# usb_host_otg.net
KiCad netlist of a schematic drawn in Altium Designer
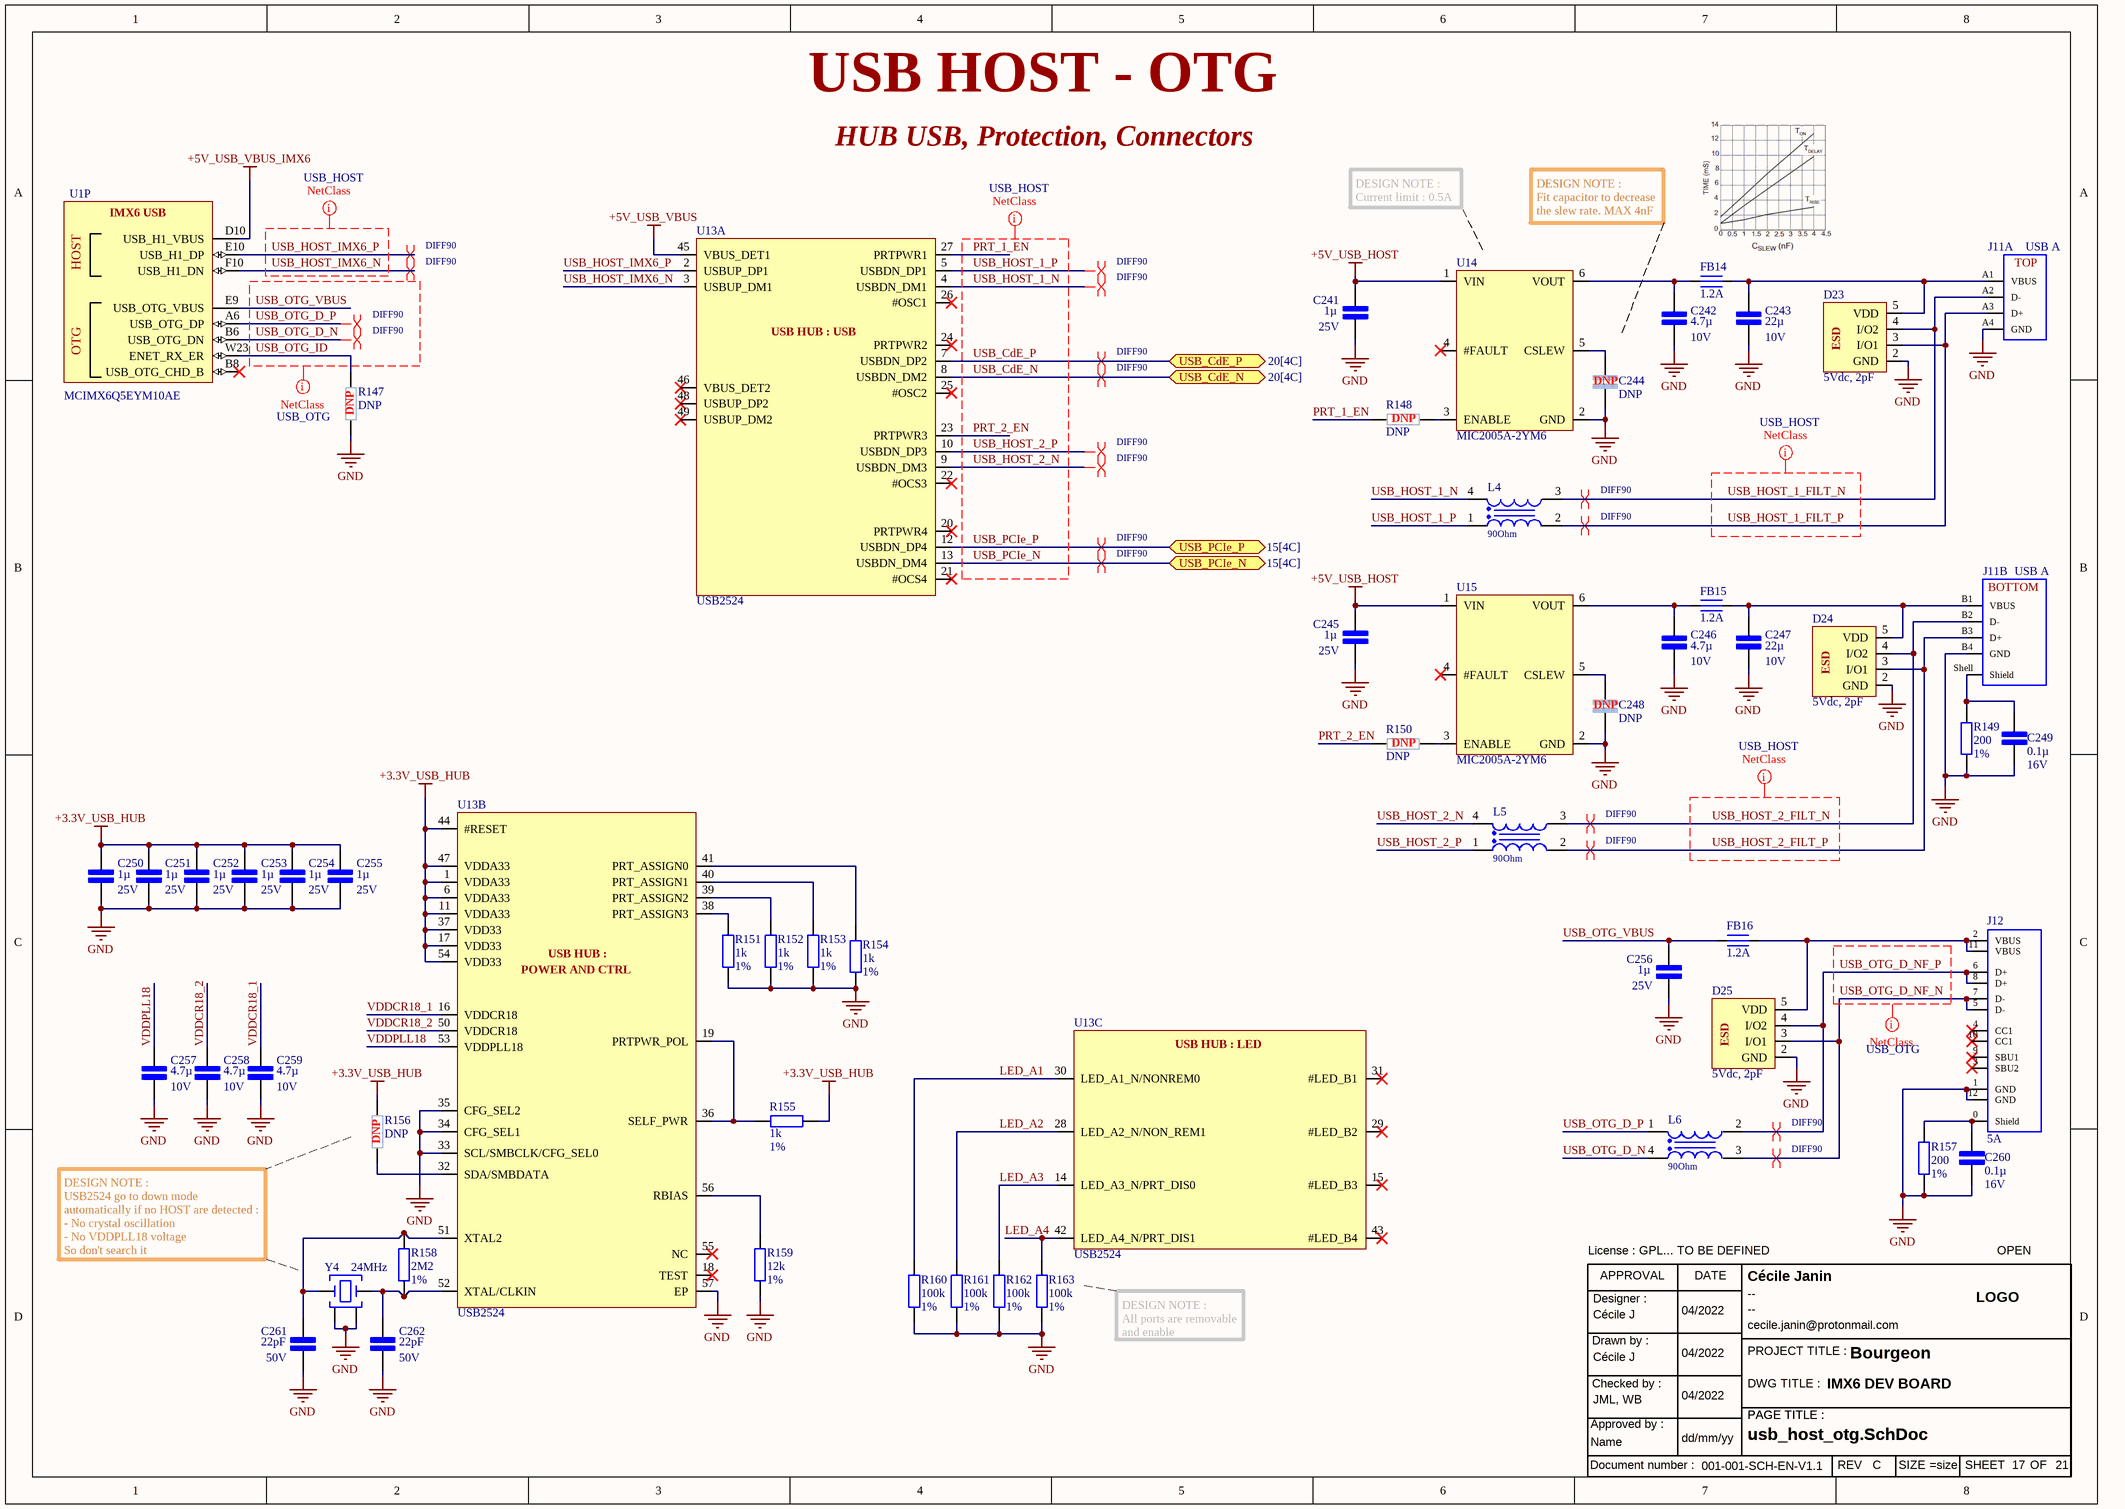
[diagram p0: usb_host_otg.SchDoc]

(export (version "E")
  (design (tool "Eeschema 10.0.6"))
  (components
    (comp (ref "C241")
      (value "1µ")
      (footprint "Cap cer 0402/1005")
      (description "cap cer 1µ 25V 10% X5R 0402")
      (fields (field (name "TENSION DU DIÉLECTRIQUE") "25V"))
      (libsource (lib "First Board IMX6") (part "cap 1µ 25V"))
    )
    (comp (ref "C242")
      (value "4.7µ")
      (footprint "Cap cer 0402/1005")
      (description "cap cer 4.7µ 10V 10% X7R 0402")
      (fields (field (name "TENSION DU DIÉLECTRIQUE") "10V"))
      (libsource (lib "First Board IMX6") (part "cap 4.7µ 10V"))
    )
    (comp (ref "C243")
      (value "22µ")
      (footprint "Cap cer 0603/4608")
      (description "cap cer 22µ 10V 10% X5R 0603")
      (fields (field (name "TENSION DU DIÉLECTRIQUE") "10V"))
      (libsource (lib "First Board IMX6") (part "cap 22µ 10V"))
    )
    (comp (ref "C244")
      (value "DNP")
      (footprint "Cap cer 0402/1005")
      (description "cap cer DNP 0402")
      (libsource (lib "First Board IMX6") (part "cap DNP"))
    )
    (comp (ref "C245")
      (value "1µ")
      (footprint "Cap cer 0402/1005")
      (description "cap cer 1µ 25V 10% X5R 0402")
      (fields (field (name "TENSION DU DIÉLECTRIQUE") "25V"))
      (libsource (lib "First Board IMX6") (part "cap 1µ 25V"))
    )
    (comp (ref "C246")
      (value "4.7µ")
      (footprint "Cap cer 0402/1005")
      (description "cap cer 4.7µ 10V 10% X7R 0402")
      (fields (field (name "TENSION DU DIÉLECTRIQUE") "10V"))
      (libsource (lib "First Board IMX6") (part "cap 4.7µ 10V"))
    )
    (comp (ref "C247")
      (value "22µ")
      (footprint "Cap cer 0603/4608")
      (description "cap cer 22µ 10V 10% X5R 0603")
      (fields (field (name "TENSION DU DIÉLECTRIQUE") "10V"))
      (libsource (lib "First Board IMX6") (part "cap 22µ 10V"))
    )
    (comp (ref "C248")
      (value "DNP")
      (footprint "Cap cer 0402/1005")
      (description "cap cer DNP 0402")
      (libsource (lib "First Board IMX6") (part "cap DNP"))
    )
    (comp (ref "C249")
      (value "0.1µ")
      (footprint "Cap cer 0402/1005")
      (description "cap solid electrolyte 0.1µ 6.3V 10%")
      (fields (field (name "TENSION DU DIÉLECTRIQUE") "16V"))
      (libsource (lib "First Board IMX6") (part "cap 0.1µ 16V"))
    )
    (comp (ref "C250")
      (value "1µ")
      (footprint "Cap cer 0402/1005")
      (description "cap cer 1µ 25V 10% X5R 0402")
      (fields (field (name "TENSION DU DIÉLECTRIQUE") "25V"))
      (libsource (lib "First Board IMX6") (part "cap 1µ 25V"))
    )
    (comp (ref "C251")
      (value "1µ")
      (footprint "Cap cer 0402/1005")
      (description "cap cer 1µ 25V 10% X5R 0402")
      (fields (field (name "TENSION DU DIÉLECTRIQUE") "25V"))
      (libsource (lib "First Board IMX6") (part "cap 1µ 25V"))
    )
    (comp (ref "C252")
      (value "1µ")
      (footprint "Cap cer 0402/1005")
      (description "cap cer 1µ 25V 10% X5R 0402")
      (fields (field (name "TENSION DU DIÉLECTRIQUE") "25V"))
      (libsource (lib "First Board IMX6") (part "cap 1µ 25V"))
    )
    (comp (ref "C253")
      (value "1µ")
      (footprint "Cap cer 0402/1005")
      (description "cap cer 1µ 25V 10% X5R 0402")
      (fields (field (name "TENSION DU DIÉLECTRIQUE") "25V"))
      (libsource (lib "First Board IMX6") (part "cap 1µ 25V"))
    )
    (comp (ref "C254")
      (value "1µ")
      (footprint "Cap cer 0402/1005")
      (description "cap cer 1µ 25V 10% X5R 0402")
      (fields (field (name "TENSION DU DIÉLECTRIQUE") "25V"))
      (libsource (lib "First Board IMX6") (part "cap 1µ 25V"))
    )
    (comp (ref "C255")
      (value "1µ")
      (footprint "Cap cer 0402/1005")
      (description "cap cer 1µ 25V 10% X5R 0402")
      (fields (field (name "TENSION DU DIÉLECTRIQUE") "25V"))
      (libsource (lib "First Board IMX6") (part "cap 1µ 25V"))
    )
    (comp (ref "C256")
      (value "1µ")
      (footprint "Cap cer 0402/1005")
      (description "cap cer 1µ 25V 10% X5R 0402")
      (fields (field (name "TENSION DU DIÉLECTRIQUE") "25V"))
      (libsource (lib "First Board IMX6") (part "cap 1µ 25V"))
    )
    (comp (ref "C257")
      (value "4.7µ")
      (footprint "Cap cer 0402/1005")
      (description "cap cer 4.7µ 10V 10% X7R 0402")
      (fields (field (name "TENSION DU DIÉLECTRIQUE") "10V"))
      (libsource (lib "First Board IMX6") (part "cap 4.7µ 10V"))
    )
    (comp (ref "C258")
      (value "4.7µ")
      (footprint "Cap cer 0402/1005")
      (description "cap cer 4.7µ 10V 10% X7R 0402")
      (fields (field (name "TENSION DU DIÉLECTRIQUE") "10V"))
      (libsource (lib "First Board IMX6") (part "cap 4.7µ 10V"))
    )
    (comp (ref "C259")
      (value "4.7µ")
      (footprint "Cap cer 0402/1005")
      (description "cap cer 4.7µ 10V 10% X7R 0402")
      (fields (field (name "TENSION DU DIÉLECTRIQUE") "10V"))
      (libsource (lib "First Board IMX6") (part "cap 4.7µ 10V"))
    )
    (comp (ref "C260")
      (value "0.1µ")
      (footprint "Cap cer 0402/1005")
      (description "cap solid electrolyte 0.1µ 6.3V 10%")
      (fields (field (name "TENSION DU DIÉLECTRIQUE") "16V"))
      (libsource (lib "First Board IMX6") (part "cap 0.1µ 16V"))
    )
    (comp (ref "C261")
      (value "22pF")
      (footprint "Cap cer 0402/1005")
      (description "cap cer 22pF 50V 5% NP0 0402")
      (fields (field (name "TENSION DU DIÉLECTRIQUE") "50V"))
      (libsource (lib "First Board IMX6") (part "cap 22pF 50V"))
    )
    (comp (ref "C262")
      (value "22pF")
      (footprint "Cap cer 0402/1005")
      (description "cap cer 22pF 50V 5% NP0 0402")
      (fields (field (name "TENSION DU DIÉLECTRIQUE") "50V"))
      (libsource (lib "First Board IMX6") (part "cap 22pF 50V"))
    )
    (comp (ref "D23")
      (value "5Vdc, 2pF")
      (footprint "Sot-23-5")
      (description "WE-TVS TVS Diode – High Speed Series, SOT23-5L, 2+1 Channel, 5Vdc, 2pF")
      (fields
        (field (name "MANUFACTURER PART NUMBER") "824011")
        (field (name "MANUFACTURER") "Wurth Elektronik")
      )
      (libsource (lib "First Board IMX6") (part "TVS USB 824011"))
    )
    (comp (ref "D24")
      (value "5Vdc, 2pF")
      (footprint "Sot-23-5")
      (description "WE-TVS TVS Diode – High Speed Series, SOT23-5L, 2+1 Channel, 5Vdc, 2pF")
      (fields
        (field (name "MANUFACTURER PART NUMBER") "824011")
        (field (name "MANUFACTURER") "Wurth Elektronik")
      )
      (libsource (lib "First Board IMX6") (part "TVS USB 824011"))
    )
    (comp (ref "D25")
      (value "5Vdc, 2pF")
      (footprint "Sot-23-5")
      (description "WE-TVS TVS Diode – High Speed Series, SOT23-5L, 2+1 Channel, 5Vdc, 2pF")
      (fields
        (field (name "MANUFACTURER PART NUMBER") "824011")
        (field (name "MANUFACTURER") "Wurth Elektronik")
      )
      (libsource (lib "First Board IMX6") (part "TVS USB 824011"))
    )
    (comp (ref "FB14")
      (value "1.2A")
      (footprint "inductor 0402/1005")
      (description "ferrite bead 1.2A 70mohm\r\n74269242111")
      (libsource (lib "First Board IMX6") (part "Ferrite bead 0402"))
    )
    (comp (ref "FB15")
      (value "1.2A")
      (footprint "inductor 0402/1005")
      (description "ferrite bead 1.2A 70mohm\r\n74269242111")
      (libsource (lib "First Board IMX6") (part "Ferrite bead 0402"))
    )
    (comp (ref "FB16")
      (value "1.2A")
      (footprint "inductor 0402/1005")
      (description "ferrite bead 1.2A 70mohm\r\n74269242111")
      (libsource (lib "First Board IMX6") (part "Ferrite bead 0402"))
    )
    (comp (ref "J11")
      (value "USB A")
      (footprint "USBA_stacked_61400826021")
      (description "2x USB type A, stacked")
      (libsource (lib "First Board IMX6") (part "USBA_stacked_61400826021"))
    )
    (comp (ref "J12")
      (value "5A")
      (footprint "USB C 12 PIN 629722000214")
      (description "629722000214 wurth connector, up to 5A")
      (libsource (lib "First Board IMX6") (part "USB C 12 pin 629722000214"))
    )
    (comp (ref "L4")
      (value "90Ohm")
      (footprint "inductor coupled usb 0603")
      (description "WE-CNSW SMT Common Mode Line Filter, size 0603, 90Ohm, 0.55A, 50V")
      (fields
        (field (name "MANUFACTURER PART NUMBER") "744230900")
        (field (name "MANUFACTURER") "Wurth Elektronik")
      )
      (libsource (lib "First Board IMX6") (part "inductor coupled USB"))
    )
    (comp (ref "L5")
      (value "90Ohm")
      (footprint "inductor coupled usb 0603")
      (description "WE-CNSW SMT Common Mode Line Filter, size 0603, 90Ohm, 0.55A, 50V")
      (fields
        (field (name "MANUFACTURER PART NUMBER") "744230900")
        (field (name "MANUFACTURER") "Wurth Elektronik")
      )
      (libsource (lib "First Board IMX6") (part "inductor coupled USB"))
    )
    (comp (ref "L6")
      (value "90Ohm")
      (footprint "inductor coupled usb 0603")
      (description "WE-CNSW SMT Common Mode Line Filter, size 0603, 90Ohm, 0.55A, 50V")
      (fields
        (field (name "MANUFACTURER PART NUMBER") "744230900")
        (field (name "MANUFACTURER") "Wurth Elektronik")
      )
      (libsource (lib "") (part "inductor coupled USB_1"))
    )
    (comp (ref "R147")
      (value "DNP")
      (footprint "Res 0402/1005")
      (description "res DNP 0403")
      (libsource (lib "First Board IMX6") (part "res DNP 0402"))
    )
    (comp (ref "R148")
      (value "DNP")
      (footprint "Res 0402/1005")
      (description "res DNP 0403")
      (libsource (lib "First Board IMX6") (part "res DNP 0402"))
    )
    (comp (ref "R149")
      (value "200")
      (footprint "Res 0402/1005")
      (description "res 200 1% 0402")
      (fields (field (name "POURCENTAGE") "1%"))
      (libsource (lib "First Board IMX6") (part "res 200 1%"))
    )
    (comp (ref "R150")
      (value "DNP")
      (footprint "Res 0402/1005")
      (description "res DNP 0403")
      (libsource (lib "First Board IMX6") (part "res DNP 0402"))
    )
    (comp (ref "R151")
      (value "1k")
      (footprint "Res 0402/1005")
      (description "res 1k 1% 0402")
      (fields (field (name "POURCENTAGE") "1%"))
      (libsource (lib "First Board IMX6") (part "res 1k 1%"))
    )
    (comp (ref "R152")
      (value "1k")
      (footprint "Res 0402/1005")
      (description "res 1k 1% 0402")
      (fields (field (name "POURCENTAGE") "1%"))
      (libsource (lib "First Board IMX6") (part "res 1k 1%"))
    )
    (comp (ref "R153")
      (value "1k")
      (footprint "Res 0402/1005")
      (description "res 1k 1% 0402")
      (fields (field (name "POURCENTAGE") "1%"))
      (libsource (lib "First Board IMX6") (part "res 1k 1%"))
    )
    (comp (ref "R154")
      (value "1k")
      (footprint "Res 0402/1005")
      (description "res 1k 1% 0402")
      (fields (field (name "POURCENTAGE") "1%"))
      (libsource (lib "First Board IMX6") (part "res 1k 1%"))
    )
    (comp (ref "R155")
      (value "1k")
      (footprint "Res 0402/1005")
      (description "res 1k 1% 0402")
      (fields (field (name "POURCENTAGE") "1%"))
      (libsource (lib "First Board IMX6") (part "res 1k 1%"))
    )
    (comp (ref "R156")
      (value "DNP")
      (footprint "Res 0402/1005")
      (description "res DNP 0403")
      (libsource (lib "First Board IMX6") (part "res DNP 0402"))
    )
    (comp (ref "R157")
      (value "200")
      (footprint "Res 0402/1005")
      (description "res 200 1% 0402")
      (fields (field (name "POURCENTAGE") "1%"))
      (libsource (lib "First Board IMX6") (part "res 200 1%"))
    )
    (comp (ref "R158")
      (value "2M2")
      (footprint "Res 0402/1005")
      (description "res 2M2 1% 0402")
      (fields (field (name "POURCENTAGE") "1%"))
      (libsource (lib "First Board IMX6") (part "res 2M2 1%"))
    )
    (comp (ref "R159")
      (value "12k")
      (footprint "Res 0402/1005")
      (description "res 12k 1% 0402")
      (fields (field (name "POURCENTAGE") "1%"))
      (libsource (lib "First Board IMX6") (part "res 12k 1%"))
    )
    (comp (ref "R160")
      (value "100k")
      (footprint "Res 0402/1005")
      (description "res 100k 1% 0402")
      (fields (field (name "POURCENTAGE") "1%"))
      (libsource (lib "First Board IMX6") (part "res 100k 1%"))
    )
    (comp (ref "R161")
      (value "100k")
      (footprint "Res 0402/1005")
      (description "res 100k 1% 0402")
      (fields (field (name "POURCENTAGE") "1%"))
      (libsource (lib "First Board IMX6") (part "res 100k 1%"))
    )
    (comp (ref "R162")
      (value "100k")
      (footprint "Res 0402/1005")
      (description "res 100k 1% 0402")
      (fields (field (name "POURCENTAGE") "1%"))
      (libsource (lib "First Board IMX6") (part "res 100k 1%"))
    )
    (comp (ref "R163")
      (value "100k")
      (footprint "Res 0402/1005")
      (description "res 100k 1% 0402")
      (fields (field (name "POURCENTAGE") "1%"))
      (libsource (lib "First Board IMX6") (part "res 100k 1%"))
    )
    (comp (ref "TB16")
      (value "Title bloc ANSI modified")
      (libsource (lib "First Board IMX6") (part "Title bloc ANSI"))
    )
    (comp (ref "U1")
      (value "MCIMX6Q5EYM10AE")
      (footprint "FRES-2197-01")
      (fields
        (field (name "PARTNUMBER") "MCIMX6Q5EYM10ACR")
        (field (name "MANUFACTURER") "Freescale Semiconductor")
      )
      (libsource (lib "First Board IMX6") (part "IMX6Q5EYM10AE"))
    )
    (comp (ref "U13")
      (value "USB2524")
      (footprint "QFN56")
      (description "USB hub 4 ports")
      (libsource (lib "First Board IMX6") (part "IC USB2524"))
    )
    (comp (ref "U14")
      (value "MIC2005A-2YM6")
      (footprint "SOt-23-6")
      (description "Current limiter 0.5A")
      (libsource (lib "First Board IMX6") (part "IC MIC2005A"))
    )
    (comp (ref "U15")
      (value "MIC2005A-2YM6")
      (footprint "SOt-23-6")
      (description "Current limiter 0.5A")
      (libsource (lib "First Board IMX6") (part "IC MIC2005A"))
    )
    (comp (ref "Y4")
      (value "24MHz")
      (footprint "IQXC-42")
      (description "WE-XTAL 24MHz, +/-10ppm\r\n830108212309")
      (fields
        (field (name "MANUFACTURER PART NUMBER") "830108212309")
        (field (name "MANUFACTURER") "Wurth Elektronik")
      )
      (libsource (lib "First Board IMX6") (part "XTAL 24MHz"))
    )
  )
  (nets
    (net (code "1") (name "+3.3V_USB_HUB") (class "Default")
      (node (ref "C250") (pin "1") (pinfunction "3_1") (pintype "passive"))
      (node (ref "C251") (pin "1") (pinfunction "3_1") (pintype "passive"))
      (node (ref "C252") (pin "1") (pinfunction "3_1") (pintype "passive"))
      (node (ref "C253") (pin "1") (pinfunction "3_1") (pintype "passive"))
      (node (ref "C254") (pin "1") (pinfunction "3_1") (pintype "passive"))
      (node (ref "C255") (pin "1") (pinfunction "3_1") (pintype "passive"))
      (node (ref "R155") (pin "2") (pintype "passive"))
      (node (ref "R156") (pin "2") (pintype "passive"))
      (node (ref "U13") (pin "1") (pinfunction "VDDA33_1") (pintype "passive"))
      (node (ref "U13") (pin "11") (pinfunction "VDDA33_11") (pintype "passive"))
      (node (ref "U13") (pin "17") (pinfunction "VDD33_17") (pintype "passive"))
      (node (ref "U13") (pin "37") (pinfunction "VDD33_37") (pintype "passive"))
      (node (ref "U13") (pin "44") (pinfunction "#RESET_44") (pintype "passive"))
      (node (ref "U13") (pin "47") (pinfunction "VDDA33_47") (pintype "passive"))
      (node (ref "U13") (pin "54") (pinfunction "VDD33_54") (pintype "passive"))
      (node (ref "U13") (pin "6") (pinfunction "VDDA33_6") (pintype "passive"))
    )
    (net (code "2") (name "+5V_USB_HOST") (class "Default")
      (node (ref "C241") (pin "1") (pinfunction "3_1") (pintype "passive"))
      (node (ref "C245") (pin "1") (pinfunction "3_1") (pintype "passive"))
      (node (ref "U14") (pin "1") (pinfunction "VIN_1") (pintype "passive"))
      (node (ref "U15") (pin "1") (pinfunction "VIN_1") (pintype "passive"))
    )
    (net (code "3") (name "+5V_USB_VBUS") (class "Default")
      (node (ref "U13") (pin "45") (pinfunction "VBUS_DET1_45") (pintype "passive"))
    )
    (net (code "4") (name "+5V_USB_VBUS_IMX6") (class "Default")
      (node (ref "U1") (pin "D10") (pinfunction "USB_H1_VBUS_D10") (pintype "power_in"))
    )
    (net (code "5") (name "/LED_A1") (class "Default")
      (node (ref "R160") (pin "2") (pintype "passive"))
      (node (ref "U13") (pin "30") (pinfunction "LED_A1_N/NONREM0_30") (pintype "passive"))
    )
    (net (code "6") (name "/LED_A2") (class "Default")
      (node (ref "R161") (pin "2") (pintype "passive"))
      (node (ref "U13") (pin "28") (pinfunction "LED_A2_N/NON_REM1_28") (pintype "passive"))
    )
    (net (code "7") (name "/LED_A3") (class "Default")
      (node (ref "R162") (pin "2") (pintype "passive"))
      (node (ref "U13") (pin "14") (pinfunction "LED_A3_N/PRT_DIS0_14") (pintype "passive"))
    )
    (net (code "8") (name "/LED_A4") (class "Default")
      (node (ref "R163") (pin "2") (pintype "passive"))
      (node (ref "U13") (pin "42") (pinfunction "LED_A4_N/PRT_DIS1_42") (pintype "passive"))
    )
    (net (code "9") (name "/PRT_1_EN") (class "Default")
      (node (ref "R148") (pin "1") (pintype "passive"))
      (node (ref "U13") (pin "27") (pinfunction "PRTPWR1_27") (pintype "passive"))
    )
    (net (code "10") (name "/PRT_2_EN") (class "Default")
      (node (ref "R150") (pin "1") (pintype "passive"))
      (node (ref "U13") (pin "23") (pinfunction "PRTPWR3_23") (pintype "passive"))
    )
    (net (code "11") (name "/USB_CdE_N") (class "Default")
      (node (ref "U13") (pin "8") (pinfunction "USBDN_DM2_8") (pintype "passive"))
    )
    (net (code "12") (name "/USB_CdE_P") (class "Default")
      (node (ref "U13") (pin "7") (pinfunction "USBDN_DP2_7") (pintype "passive"))
    )
    (net (code "13") (name "/USB_HOST_1_FILT_N") (class "Default")
      (node (ref "D23") (pin "4") (pinfunction "I/O2_4") (pintype "passive"))
      (node (ref "J11") (pin "A2") (pinfunction "D-_A2") (pintype "passive"))
      (node (ref "L4") (pin "3") (pinfunction "3_3") (pintype "passive"))
    )
    (net (code "14") (name "/USB_HOST_1_FILT_P") (class "Default")
      (node (ref "D23") (pin "3") (pinfunction "I/O1_3") (pintype "passive"))
      (node (ref "J11") (pin "A3") (pinfunction "D+_A3") (pintype "passive"))
      (node (ref "L4") (pin "2") (pinfunction "2_2") (pintype "passive"))
    )
    (net (code "15") (name "/USB_HOST_1_N") (class "Default")
      (node (ref "L4") (pin "4") (pinfunction "4_4") (pintype "passive"))
      (node (ref "U13") (pin "4") (pinfunction "USBDN_DM1_4") (pintype "passive"))
    )
    (net (code "16") (name "/USB_HOST_1_P") (class "Default")
      (node (ref "L4") (pin "1") (pinfunction "1_1") (pintype "passive"))
      (node (ref "U13") (pin "5") (pinfunction "USBDN_DP1_5") (pintype "passive"))
    )
    (net (code "17") (name "/USB_HOST_2_FILT_N") (class "Default")
      (node (ref "D24") (pin "4") (pinfunction "I/O2_4") (pintype "passive"))
      (node (ref "J11") (pin "B2") (pinfunction "D-_B2") (pintype "passive"))
      (node (ref "L5") (pin "3") (pinfunction "3_3") (pintype "passive"))
    )
    (net (code "18") (name "/USB_HOST_2_FILT_P") (class "Default")
      (node (ref "D24") (pin "3") (pinfunction "I/O1_3") (pintype "passive"))
      (node (ref "J11") (pin "B3") (pinfunction "D+_B3") (pintype "passive"))
      (node (ref "L5") (pin "2") (pinfunction "2_2") (pintype "passive"))
    )
    (net (code "19") (name "/USB_HOST_2_N") (class "Default")
      (node (ref "L5") (pin "4") (pinfunction "4_4") (pintype "passive"))
      (node (ref "U13") (pin "9") (pinfunction "USBDN_DM3_9") (pintype "passive"))
    )
    (net (code "20") (name "/USB_HOST_2_P") (class "Default")
      (node (ref "L5") (pin "1") (pinfunction "1_1") (pintype "passive"))
      (node (ref "U13") (pin "10") (pinfunction "USBDN_DP3_10") (pintype "passive"))
    )
    (net (code "21") (name "/USB_HOST_IMX6_N") (class "Default")
      (node (ref "U1") (pin "F10") (pinfunction "USB_H1_DN_F10") (pintype "bidirectional"))
      (node (ref "U13") (pin "3") (pinfunction "USBUP_DM1_3") (pintype "passive"))
    )
    (net (code "22") (name "/USB_HOST_IMX6_P") (class "Default")
      (node (ref "U1") (pin "E10") (pinfunction "USB_H1_DP_E10") (pintype "bidirectional"))
      (node (ref "U13") (pin "2") (pinfunction "USBUP_DP1_2") (pintype "passive"))
    )
    (net (code "23") (name "/USB_OTG_D_N") (class "Default")
      (node (ref "L6") (pin "4") (pinfunction "4_4") (pintype "passive"))
      (node (ref "U1") (pin "B6") (pinfunction "USB_OTG_DN_B6") (pintype "bidirectional"))
    )
    (net (code "24") (name "/USB_OTG_D_NF_N") (class "Default")
      (node (ref "D25") (pin "3") (pinfunction "I/O1_3") (pintype "passive"))
      (node (ref "J12") (pin "5") (pinfunction "D-_5") (pintype "passive"))
      (node (ref "J12") (pin "7") (pinfunction "D-_7") (pintype "passive"))
      (node (ref "L6") (pin "3") (pinfunction "3_3") (pintype "passive"))
    )
    (net (code "25") (name "/USB_OTG_D_NF_P") (class "Default")
      (node (ref "D25") (pin "4") (pinfunction "I/O2_4") (pintype "passive"))
      (node (ref "J12") (pin "6") (pinfunction "D+_6") (pintype "passive"))
      (node (ref "J12") (pin "8") (pinfunction "D+_8") (pintype "passive"))
      (node (ref "L6") (pin "2") (pinfunction "2_2") (pintype "passive"))
    )
    (net (code "26") (name "/USB_OTG_D_P") (class "Default")
      (node (ref "L6") (pin "1") (pinfunction "1_1") (pintype "passive"))
      (node (ref "U1") (pin "A6") (pinfunction "USB_OTG_DP_A6") (pintype "bidirectional"))
    )
    (net (code "27") (name "/USB_OTG_ID") (class "Default")
      (node (ref "R147") (pin "2") (pintype "passive"))
      (node (ref "U1") (pin "W23") (pinfunction "ENET_RX_ER_W23") (pintype "bidirectional"))
    )
    (net (code "28") (name "/USB_OTG_VBUS") (class "Default")
      (node (ref "C256") (pin "1") (pinfunction "3_1") (pintype "passive"))
      (node (ref "FB16") (pin "1") (pinfunction "1_1") (pintype "passive"))
      (node (ref "U1") (pin "E9") (pinfunction "USB_OTG_VBUS_E9") (pintype "power_in"))
    )
    (net (code "29") (name "/USB_PCIe_N") (class "Default")
      (node (ref "U13") (pin "13") (pinfunction "USBDN_DM4_13") (pintype "passive"))
    )
    (net (code "30") (name "/USB_PCIe_P") (class "Default")
      (node (ref "U13") (pin "12") (pinfunction "USBDN_DP4_12") (pintype "passive"))
    )
    (net (code "31") (name "/VDDCR18_1") (class "Default")
      (node (ref "C259") (pin "1") (pinfunction "3_1") (pintype "passive"))
      (node (ref "U13") (pin "16") (pinfunction "VDDCR18_16") (pintype "passive"))
    )
    (net (code "32") (name "/VDDCR18_2") (class "Default")
      (node (ref "C258") (pin "1") (pinfunction "3_1") (pintype "passive"))
      (node (ref "U13") (pin "50") (pinfunction "VDDCR18_50") (pintype "passive"))
    )
    (net (code "33") (name "/VDDPLL18") (class "Default")
      (node (ref "C257") (pin "1") (pinfunction "3_1") (pintype "passive"))
      (node (ref "U13") (pin "53") (pinfunction "VDDPLL18_53") (pintype "passive"))
    )
    (net (code "34") (name "GND") (class "Default")
      (node (ref "C241") (pin "2") (pinfunction "4_2") (pintype "passive"))
      (node (ref "C242") (pin "2") (pinfunction "4_2") (pintype "passive"))
      (node (ref "C243") (pin "2") (pinfunction "4_2") (pintype "passive"))
      (node (ref "C244") (pin "2") (pinfunction "4_2") (pintype "passive"))
      (node (ref "C245") (pin "2") (pinfunction "4_2") (pintype "passive"))
      (node (ref "C246") (pin "2") (pinfunction "4_2") (pintype "passive"))
      (node (ref "C247") (pin "2") (pinfunction "4_2") (pintype "passive"))
      (node (ref "C248") (pin "2") (pinfunction "4_2") (pintype "passive"))
      (node (ref "C249") (pin "2") (pinfunction "4_2") (pintype "passive"))
      (node (ref "C250") (pin "2") (pinfunction "4_2") (pintype "passive"))
      (node (ref "C251") (pin "2") (pinfunction "4_2") (pintype "passive"))
      (node (ref "C252") (pin "2") (pinfunction "4_2") (pintype "passive"))
      (node (ref "C253") (pin "2") (pinfunction "4_2") (pintype "passive"))
      (node (ref "C254") (pin "2") (pinfunction "4_2") (pintype "passive"))
      (node (ref "C255") (pin "2") (pinfunction "4_2") (pintype "passive"))
      (node (ref "C256") (pin "2") (pinfunction "4_2") (pintype "passive"))
      (node (ref "C257") (pin "2") (pinfunction "4_2") (pintype "passive"))
      (node (ref "C258") (pin "2") (pinfunction "4_2") (pintype "passive"))
      (node (ref "C259") (pin "2") (pinfunction "4_2") (pintype "passive"))
      (node (ref "C260") (pin "2") (pinfunction "4_2") (pintype "passive"))
      (node (ref "C261") (pin "2") (pinfunction "4_2") (pintype "passive"))
      (node (ref "C262") (pin "2") (pinfunction "4_2") (pintype "passive"))
      (node (ref "D23") (pin "2") (pinfunction "GND_2") (pintype "passive"))
      (node (ref "D24") (pin "2") (pinfunction "GND_2") (pintype "passive"))
      (node (ref "D25") (pin "2") (pinfunction "GND_2") (pintype "passive"))
      (node (ref "J11") (pin "A4") (pinfunction "GND_A4") (pintype "passive"))
      (node (ref "J11") (pin "B4") (pinfunction "GND_B4") (pintype "passive"))
      (node (ref "J12") (pin "1") (pinfunction "GND_1") (pintype "passive"))
      (node (ref "J12") (pin "12") (pinfunction "GND_12") (pintype "passive"))
      (node (ref "R147") (pin "1") (pintype "passive"))
      (node (ref "R149") (pin "1") (pintype "passive"))
      (node (ref "R151") (pin "1") (pintype "passive"))
      (node (ref "R152") (pin "1") (pintype "passive"))
      (node (ref "R153") (pin "1") (pintype "passive"))
      (node (ref "R154") (pin "1") (pintype "passive"))
      (node (ref "R157") (pin "1") (pintype "passive"))
      (node (ref "R159") (pin "1") (pintype "passive"))
      (node (ref "R160") (pin "1") (pintype "passive"))
      (node (ref "R161") (pin "1") (pintype "passive"))
      (node (ref "R162") (pin "1") (pintype "passive"))
      (node (ref "R163") (pin "1") (pintype "passive"))
      (node (ref "U13") (pin "33") (pinfunction "SCL/SMBCLK/CFG_SEL0_33") (pintype "passive"))
      (node (ref "U13") (pin "34") (pinfunction "CFG_SEL1_34") (pintype "passive"))
      (node (ref "U13") (pin "35") (pinfunction "CFG_SEL2_35") (pintype "passive"))
      (node (ref "U13") (pin "57") (pinfunction "EP_57") (pintype "passive"))
      (node (ref "U14") (pin "2") (pinfunction "GND_2") (pintype "passive"))
      (node (ref "U15") (pin "2") (pinfunction "GND_2") (pintype "passive"))
      (node (ref "Y4") (pin "2") (pinfunction "GND_2") (pintype "passive"))
      (node (ref "Y4") (pin "4") (pinfunction "GND_4") (pintype "passive"))
    )
    (net (code "35") (name "Net-(C242-3)") (class "Default")
      (node (ref "C242") (pin "1") (pinfunction "3_1") (pintype "passive"))
      (node (ref "FB14") (pin "1") (pinfunction "1_1") (pintype "passive"))
      (node (ref "U14") (pin "6") (pinfunction "VOUT_6") (pintype "passive"))
    )
    (net (code "36") (name "Net-(C243-3)") (class "Default")
      (node (ref "C243") (pin "1") (pinfunction "3_1") (pintype "passive"))
      (node (ref "D23") (pin "5") (pinfunction "VDD_5") (pintype "passive"))
      (node (ref "FB14") (pin "2") (pinfunction "2_2") (pintype "passive"))
      (node (ref "J11") (pin "A1") (pinfunction "VBUS_A1") (pintype "passive"))
    )
    (net (code "37") (name "Net-(C244-3)") (class "Default")
      (node (ref "C244") (pin "1") (pinfunction "3_1") (pintype "passive"))
      (node (ref "U14") (pin "5") (pinfunction "CSLEW_5") (pintype "passive"))
    )
    (net (code "38") (name "Net-(C246-3)") (class "Default")
      (node (ref "C246") (pin "1") (pinfunction "3_1") (pintype "passive"))
      (node (ref "FB15") (pin "1") (pinfunction "1_1") (pintype "passive"))
      (node (ref "U15") (pin "6") (pinfunction "VOUT_6") (pintype "passive"))
    )
    (net (code "39") (name "Net-(C247-3)") (class "Default")
      (node (ref "C247") (pin "1") (pinfunction "3_1") (pintype "passive"))
      (node (ref "D24") (pin "5") (pinfunction "VDD_5") (pintype "passive"))
      (node (ref "FB15") (pin "2") (pinfunction "2_2") (pintype "passive"))
      (node (ref "J11") (pin "B1") (pinfunction "VBUS_B1") (pintype "passive"))
    )
    (net (code "40") (name "Net-(C248-3)") (class "Default")
      (node (ref "C248") (pin "1") (pinfunction "3_1") (pintype "passive"))
      (node (ref "U15") (pin "5") (pinfunction "CSLEW_5") (pintype "passive"))
    )
    (net (code "41") (name "Net-(C249-3)") (class "Default")
      (node (ref "C249") (pin "1") (pinfunction "3_1") (pintype "passive"))
      (node (ref "J11") (pin "Shell") (pinfunction "Shield_Shell") (pintype "passive"))
      (node (ref "R149") (pin "2") (pintype "passive"))
    )
    (net (code "42") (name "Net-(C260-3)") (class "Default")
      (node (ref "C260") (pin "1") (pinfunction "3_1") (pintype "passive"))
      (node (ref "J12") (pin "0") (pinfunction "Shield_0") (pintype "passive"))
      (node (ref "R157") (pin "2") (pintype "passive"))
    )
    (net (code "43") (name "Net-(C261-3)") (class "Default")
      (node (ref "C261") (pin "1") (pinfunction "3_1") (pintype "passive"))
      (node (ref "R158") (pin "2") (pintype "passive"))
      (node (ref "U13") (pin "51") (pinfunction "XTAL2_51") (pintype "passive"))
      (node (ref "Y4") (pin "3") (pinfunction "Crystal_3") (pintype "passive"))
    )
    (net (code "44") (name "Net-(C262-3)") (class "Default")
      (node (ref "C262") (pin "1") (pinfunction "3_1") (pintype "passive"))
      (node (ref "R158") (pin "1") (pintype "passive"))
      (node (ref "U13") (pin "52") (pinfunction "XTAL/CLKIN_52") (pintype "passive"))
      (node (ref "Y4") (pin "1") (pinfunction "Crystal_1") (pintype "passive"))
    )
    (net (code "45") (name "Net-(D25-VDD)") (class "Default")
      (node (ref "D25") (pin "5") (pinfunction "VDD_5") (pintype "passive"))
      (node (ref "FB16") (pin "2") (pinfunction "2_2") (pintype "passive"))
      (node (ref "J12") (pin "11") (pinfunction "VBUS_11") (pintype "passive"))
      (node (ref "J12") (pin "2") (pinfunction "VBUS_2") (pintype "passive"))
    )
    (net (code "46") (name "Net-(U13B-PRTPWR_POL)") (class "Default")
      (node (ref "R155") (pin "1") (pintype "passive"))
      (node (ref "U13") (pin "19") (pinfunction "PRTPWR_POL_19") (pintype "passive"))
      (node (ref "U13") (pin "36") (pinfunction "SELF_PWR_36") (pintype "passive"))
    )
    (net (code "47") (name "Net-(U13B-PRT_ASSIGN0)") (class "Default")
      (node (ref "R154") (pin "2") (pintype "passive"))
      (node (ref "U13") (pin "41") (pinfunction "PRT_ASSIGN0_41") (pintype "passive"))
    )
    (net (code "48") (name "Net-(U13B-PRT_ASSIGN1)") (class "Default")
      (node (ref "R153") (pin "2") (pintype "passive"))
      (node (ref "U13") (pin "40") (pinfunction "PRT_ASSIGN1_40") (pintype "passive"))
    )
    (net (code "49") (name "Net-(U13B-PRT_ASSIGN2)") (class "Default")
      (node (ref "R152") (pin "2") (pintype "passive"))
      (node (ref "U13") (pin "39") (pinfunction "PRT_ASSIGN2_39") (pintype "passive"))
    )
    (net (code "50") (name "Net-(U13B-PRT_ASSIGN3)") (class "Default")
      (node (ref "R151") (pin "2") (pintype "passive"))
      (node (ref "U13") (pin "38") (pinfunction "PRT_ASSIGN3_38") (pintype "passive"))
    )
    (net (code "51") (name "Net-(U13B-RBIAS)") (class "Default")
      (node (ref "R159") (pin "2") (pintype "passive"))
      (node (ref "U13") (pin "56") (pinfunction "RBIAS_56") (pintype "passive"))
    )
    (net (code "52") (name "Net-(U13B-SDA{slash}SMBDATA)") (class "Default")
      (node (ref "R156") (pin "1") (pintype "passive"))
      (node (ref "U13") (pin "32") (pinfunction "SDA/SMBDATA_32") (pintype "passive"))
    )
    (net (code "53") (name "Net-(U14-ENABLE)") (class "Default")
      (node (ref "R148") (pin "2") (pintype "passive"))
      (node (ref "U14") (pin "3") (pinfunction "ENABLE_3") (pintype "passive"))
    )
    (net (code "54") (name "Net-(U15-ENABLE)") (class "Default")
      (node (ref "R150") (pin "2") (pintype "passive"))
      (node (ref "U15") (pin "3") (pinfunction "ENABLE_3") (pintype "passive"))
    )
    (net (code "55") (name "unconnected-(J12-CC1-Pad4)") (class "Default")
      (node (ref "J12") (pin "4") (pinfunction "CC1_4") (pintype "passive+no_connect"))
    )
    (net (code "56") (name "unconnected-(J12-CC1-Pad10)") (class "Default")
      (node (ref "J12") (pin "10") (pinfunction "CC1_10") (pintype "passive+no_connect"))
    )
    (net (code "57") (name "unconnected-(J12-SBU1-Pad9)") (class "Default")
      (node (ref "J12") (pin "9") (pinfunction "SBU1_9") (pintype "passive+no_connect"))
    )
    (net (code "58") (name "unconnected-(J12-SBU2-Pad3)") (class "Default")
      (node (ref "J12") (pin "3") (pinfunction "SBU2_3") (pintype "passive+no_connect"))
    )
    (net (code "59") (name "unconnected-(U1P-USB_OTG_CHD_B-PadB8)") (class "Default")
      (node (ref "U1") (pin "B8") (pinfunction "USB_OTG_CHD_B_B8") (pintype "bidirectional+no_connect"))
    )
    (net (code "60") (name "unconnected-(U13A-#OCS3-Pad22)") (class "Default")
      (node (ref "U13") (pin "22") (pinfunction "#OCS3_22") (pintype "passive+no_connect"))
    )
    (net (code "61") (name "unconnected-(U13A-#OCS4-Pad21)") (class "Default")
      (node (ref "U13") (pin "21") (pinfunction "#OCS4_21") (pintype "passive+no_connect"))
    )
    (net (code "62") (name "unconnected-(U13A-#OSC1-Pad26)") (class "Default")
      (node (ref "U13") (pin "26") (pinfunction "#OSC1_26") (pintype "passive+no_connect"))
    )
    (net (code "63") (name "unconnected-(U13A-#OSC2-Pad25)") (class "Default")
      (node (ref "U13") (pin "25") (pinfunction "#OSC2_25") (pintype "passive+no_connect"))
    )
    (net (code "64") (name "unconnected-(U13A-PRTPWR2-Pad24)") (class "Default")
      (node (ref "U13") (pin "24") (pinfunction "PRTPWR2_24") (pintype "passive+no_connect"))
    )
    (net (code "65") (name "unconnected-(U13A-PRTPWR4-Pad20)") (class "Default")
      (node (ref "U13") (pin "20") (pinfunction "PRTPWR4_20") (pintype "passive+no_connect"))
    )
    (net (code "66") (name "unconnected-(U13A-USBUP_DM2-Pad49)") (class "Default")
      (node (ref "U13") (pin "49") (pinfunction "USBUP_DM2_49") (pintype "passive+no_connect"))
    )
    (net (code "67") (name "unconnected-(U13A-USBUP_DP2-Pad48)") (class "Default")
      (node (ref "U13") (pin "48") (pinfunction "USBUP_DP2_48") (pintype "passive+no_connect"))
    )
    (net (code "68") (name "unconnected-(U13A-VBUS_DET2-Pad46)") (class "Default")
      (node (ref "U13") (pin "46") (pinfunction "VBUS_DET2_46") (pintype "passive+no_connect"))
    )
    (net (code "69") (name "unconnected-(U13B-NC-Pad55)") (class "Default")
      (node (ref "U13") (pin "55") (pinfunction "NC_55") (pintype "passive+no_connect"))
    )
    (net (code "70") (name "unconnected-(U13B-TEST-Pad18)") (class "Default")
      (node (ref "U13") (pin "18") (pinfunction "TEST_18") (pintype "passive+no_connect"))
    )
    (net (code "71") (name "unconnected-(U13C-#LED_B1-Pad31)") (class "Default")
      (node (ref "U13") (pin "31") (pinfunction "#LED_B1_31") (pintype "passive+no_connect"))
    )
    (net (code "72") (name "unconnected-(U13C-#LED_B2-Pad29)") (class "Default")
      (node (ref "U13") (pin "29") (pinfunction "#LED_B2_29") (pintype "passive+no_connect"))
    )
    (net (code "73") (name "unconnected-(U13C-#LED_B3-Pad15)") (class "Default")
      (node (ref "U13") (pin "15") (pinfunction "#LED_B3_15") (pintype "passive+no_connect"))
    )
    (net (code "74") (name "unconnected-(U13C-#LED_B4-Pad43)") (class "Default")
      (node (ref "U13") (pin "43") (pinfunction "#LED_B4_43") (pintype "passive+no_connect"))
    )
    (net (code "75") (name "unconnected-(U14-#FAULT-Pad4)") (class "Default")
      (node (ref "U14") (pin "4") (pinfunction "#FAULT_4") (pintype "passive+no_connect"))
    )
    (net (code "76") (name "unconnected-(U15-#FAULT-Pad4)") (class "Default")
      (node (ref "U15") (pin "4") (pinfunction "#FAULT_4") (pintype "passive+no_connect"))
    )
  )
)
